# ife19_TS_TSAL-Discharge-TSMP.net
KiCad netlist of a schematic drawn in Altium Designer
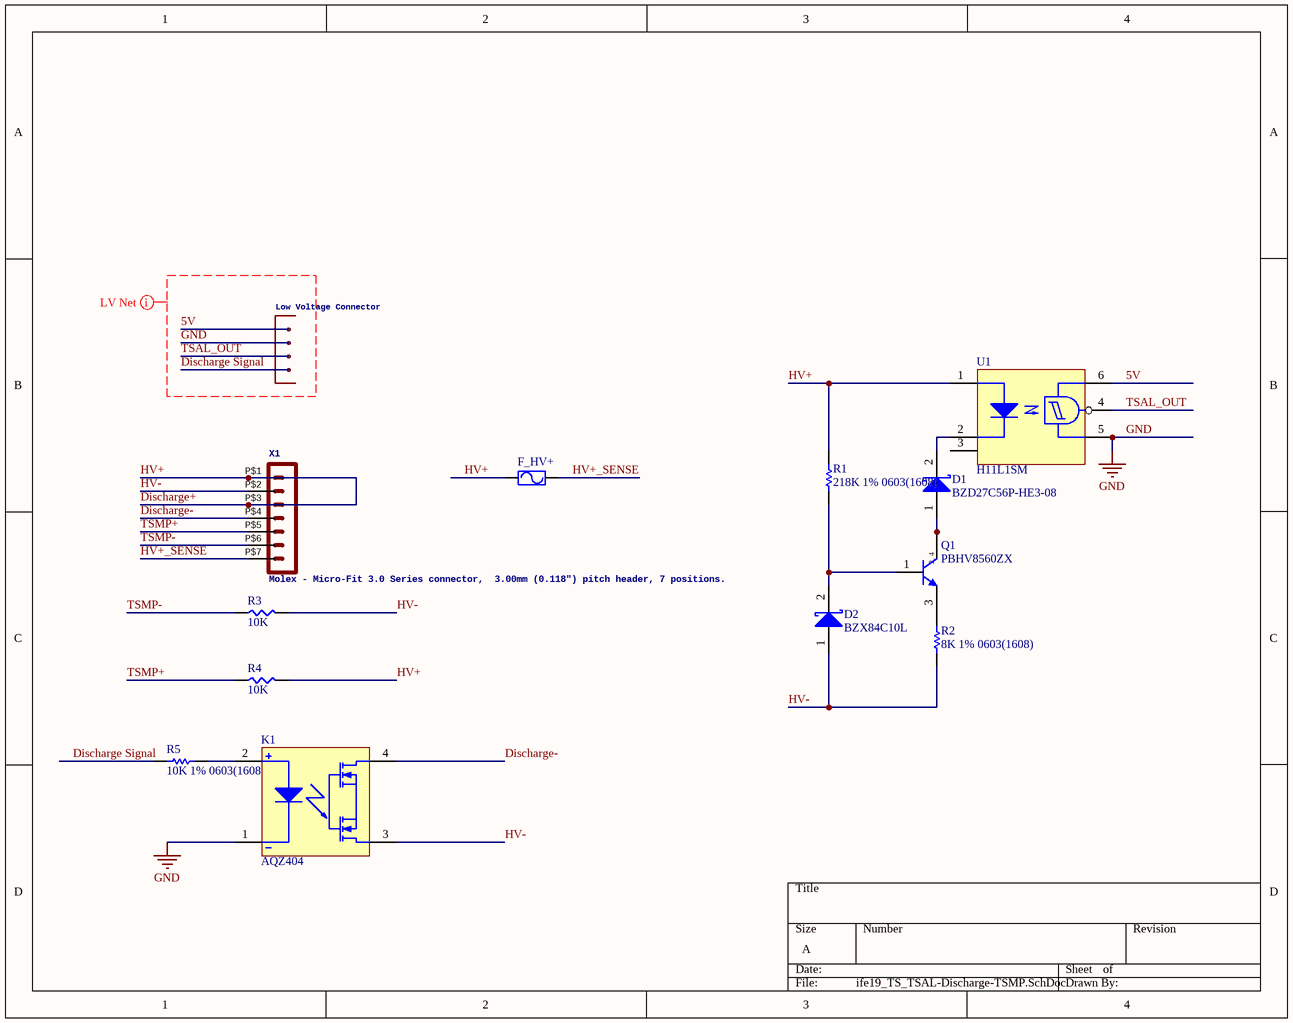
[diagram p0: ife19_TS_TSAL-Discharge-TSMP.SchDoc]

(export (version "E")
  (design (tool "Eeschema 10.0.6"))
  (components
    (comp (ref "D1")
      (value "BZD27C56P-HE3-08")
      (footprint "VISH-DO-219AB_V")
      (description "Schottky Rectifier, 30 V, 1.1 A, 2-Pin DO-219AB (SMF), RoHS, Tape and Reel")
      (fields (field (name "PARTNUMBER") "SL03-GS08CT") (field (name "MANUFACTURER") "Vishay Semiconductor"))
      (libsource (lib "Altium Content Vault") (part "DSKY-AK-2"))
    )
    (comp (ref "D2")
      (value "BZX84C10L")
      (footprint "VISH-DO-219AB_V")
      (description "Schottky Rectifier, 30 V, 1.1 A, 2-Pin DO-219AB (SMF), RoHS, Tape and Reel")
      (fields (field (name "PARTNUMBER") "SL03-GS08CT") (field (name "MANUFACTURER") "Vishay Semiconductor"))
      (libsource (lib "Altium Content Vault") (part "DSKY-AK-2"))
    )
    (comp (ref "F_HV+")
      (value "FUSE_885")
      (footprint "FUSE_885")
      (libsource (lib "altium-import") (part "root_0_FUSE_885_"))
    )
    (comp (ref "K1")
      (value "AQZ404")
      (footprint "PNSC-SIL4_V")
      (fields (field (name "MANUFACTURER") "Panasonic"))
      (libsource (lib "Altium Content Vault") (part "PNSC-AQZX0X-SIL4"))
    )
    (comp (ref "Low Voltage Connector")
      (value "~")
      (footprint "505575-04")
      (fields (field (name "LIBRARYNAME") "MOLEX Micro-Lock"))
      (libsource (lib "MOLEX Micro-Lock (2)") (part "505575-04"))
    )
    (comp (ref "Q1")
      (value "PBHV8560ZX")
      (footprint "NXP-SOT223_L")
      (description "NPN Medium Power Transistor, 60 V, 1 A, -55 to 150 degC, 4-Pin SOT223, RoHS, Tape and Reel")
      (fields (field (name "MANUFACTURER") "NXP Semiconductors"))
      (libsource (lib "Altium Content Vault") (part "BJT-NPN-BCEC-4"))
    )
    (comp (ref "R1")
      (value "218K 1% 0603(1608)")
      (footprint "RESC0603(1608)_L")
      (description "249K 0.1W 1% 0603 (1608 Metric)  SMD")
      (fields (field (name "POWER") "0.1 W") (field (name "TOLERANCE") "1 %"))
      (libsource (lib "Altium Content Vault") (part "RES"))
    )
    (comp (ref "R2")
      (value "8K 1% 0603(1608)")
      (footprint "RESC0603(1608)_L")
      (description "348K 0.1W 1% 0603 (1608 Metric)  SMD")
      (fields (field (name "TOLERANCE") "1 %") (field (name "POWER") "0.1 W"))
      (libsource (lib "Altium Content Vault") (part "RES"))
    )
    (comp (ref "R3")
      (value "10K")
      (footprint "Ohmite 45")
      (libsource (lib "IFE_Resistors (2)") (part "Ohmite 40 Series"))
    )
    (comp (ref "R4")
      (value "10K")
      (footprint "Ohmite 45")
      (libsource (lib "IFE_Resistors (2)") (part "Ohmite 40 Series"))
    )
    (comp (ref "R5")
      (value "10K 1% 0603(1608)")
      (footprint "RESC0603(1608)_L")
      (description "249K 0.1W 1% 0603 (1608 Metric)  SMD")
      (fields (field (name "POWER") "0.1 W") (field (name "TOLERANCE") "1 %"))
      (libsource (lib "Altium Content Vault") (part "RES"))
    )
    (comp (ref "U1")
      (value "H11L1SM")
      (footprint "FAIR-SMT-6_V")
      (description "Schmitt Trigger Output Optocoupler, 3 to 15 V, -40 to 85 degC, 6-Pin SMT, RoHS, Tube")
      (fields (field (name "MANUFACTURER") "Fairchild Semiconductor"))
      (libsource (lib "Altium Content Vault") (part "FAIR-H11L1M-6"))
    )
    (comp (ref "X1")
      (value "Molex - Micro-Fit 3.0 Series connector,  3.00mm (0.118\") pitch header, 7 positions.")
      (footprint "43650-0724")
      (libsource (lib "altium-import") (part "root_0_POS7_MF43650-0724_"))
    )
  )
  (nets
    (net (code "1") (name "/5V") (class "Default")
      (node (ref "Low Voltage Connector") (pin "1") (pinfunction "1_1") (pintype "passive"))
      (node (ref "U1") (pin "6") (pinfunction "VCC_6") (pintype "power_in"))
    )
    (net (code "2") (name "/Discharge Signal") (class "Default")
      (node (ref "Low Voltage Connector") (pin "4") (pinfunction "4_4") (pintype "passive"))
      (node (ref "R5") (pin "2") (pinfunction "2_2") (pintype "passive"))
    )
    (net (code "3") (name "/Discharge+") (class "Default")
      (node (ref "F_HV+") (pin "2") (pinfunction "2_2") (pintype "passive"))
      (node (ref "R1") (pin "2") (pinfunction "2_2") (pintype "passive"))
      (node (ref "R4") (pin "2") (pinfunction "2_2") (pintype "passive"))
      (node (ref "U1") (pin "1") (pinfunction "ANODE_1") (pintype "passive"))
      (node (ref "X1") (pin "P$1") (pinfunction "1_P$1") (pintype "passive"))
      (node (ref "X1") (pin "P$3") (pinfunction "3_P$3") (pintype "passive"))
    )
    (net (code "4") (name "/Discharge-") (class "Default")
      (node (ref "K1") (pin "4") (pinfunction "4_4") (pintype "passive"))
      (node (ref "X1") (pin "P$4") (pinfunction "4_P$4") (pintype "passive"))
    )
    (net (code "5") (name "/HV+_SENSE") (class "Default")
      (node (ref "F_HV+") (pin "1") (pinfunction "1_1") (pintype "passive"))
      (node (ref "X1") (pin "P$7") (pinfunction "7_P$7") (pintype "passive"))
    )
    (net (code "6") (name "/HV-") (class "Default")
      (node (ref "D2") (pin "1") (pinfunction "A_1") (pintype "passive"))
      (node (ref "K1") (pin "3") (pinfunction "3_3") (pintype "passive"))
      (node (ref "R2") (pin "1") (pinfunction "1_1") (pintype "passive"))
      (node (ref "R3") (pin "2") (pinfunction "2_2") (pintype "passive"))
      (node (ref "X1") (pin "P$2") (pinfunction "2_P$2") (pintype "passive"))
    )
    (net (code "7") (name "/TSAL_OUT") (class "Default")
      (node (ref "Low Voltage Connector") (pin "3") (pinfunction "3_3") (pintype "passive"))
      (node (ref "U1") (pin "4") (pinfunction "VO_4") (pintype "open_collector"))
    )
    (net (code "8") (name "/TSMP+") (class "Default")
      (node (ref "R4") (pin "1") (pinfunction "1_1") (pintype "passive"))
      (node (ref "X1") (pin "P$5") (pinfunction "5_P$5") (pintype "passive"))
    )
    (net (code "9") (name "/TSMP-") (class "Default")
      (node (ref "R3") (pin "1") (pinfunction "1_1") (pintype "passive"))
      (node (ref "X1") (pin "P$6") (pinfunction "6_P$6") (pintype "passive"))
    )
    (net (code "10") (name "GND") (class "Default")
      (node (ref "K1") (pin "1") (pinfunction "-_1") (pintype "passive"))
      (node (ref "Low Voltage Connector") (pin "2") (pinfunction "2_2") (pintype "passive"))
      (node (ref "U1") (pin "5") (pinfunction "GND_5") (pintype "power_in"))
    )
    (net (code "11") (name "Net-(D1-A)") (class "Default")
      (node (ref "D1") (pin "1") (pinfunction "A_1") (pintype "passive"))
      (node (ref "Q1") (pin "2") (pinfunction "C_2") (pintype "passive"))
      (node (ref "Q1") (pin "4") (pinfunction "C_4") (pintype "passive"))
    )
    (net (code "12") (name "Net-(D1-K)") (class "Default")
      (node (ref "D1") (pin "2") (pinfunction "K_2") (pintype "passive"))
      (node (ref "U1") (pin "2") (pinfunction "CATHODE_2") (pintype "passive"))
    )
    (net (code "13") (name "Net-(D2-K)") (class "Default")
      (node (ref "D2") (pin "2") (pinfunction "K_2") (pintype "passive"))
      (node (ref "Q1") (pin "1") (pinfunction "B_1") (pintype "passive"))
      (node (ref "R1") (pin "1") (pinfunction "1_1") (pintype "passive"))
    )
    (net (code "14") (name "Net-(K1-+)") (class "Default")
      (node (ref "K1") (pin "2") (pinfunction "+_2") (pintype "passive"))
      (node (ref "R5") (pin "1") (pinfunction "1_1") (pintype "passive"))
    )
    (net (code "15") (name "Net-(Q1-E)") (class "Default")
      (node (ref "Q1") (pin "3") (pinfunction "E_3") (pintype "passive"))
      (node (ref "R2") (pin "2") (pinfunction "2_2") (pintype "passive"))
    )
    (net (code "16") (name "unconnected-(U1-NC-Pad3)") (class "Default")
      (node (ref "U1") (pin "3") (pinfunction "NC_3") (pintype "passive"))
    )
  )
)
